# AdaPoon.net
KiCad netlist of a schematic drawn in EAGLE
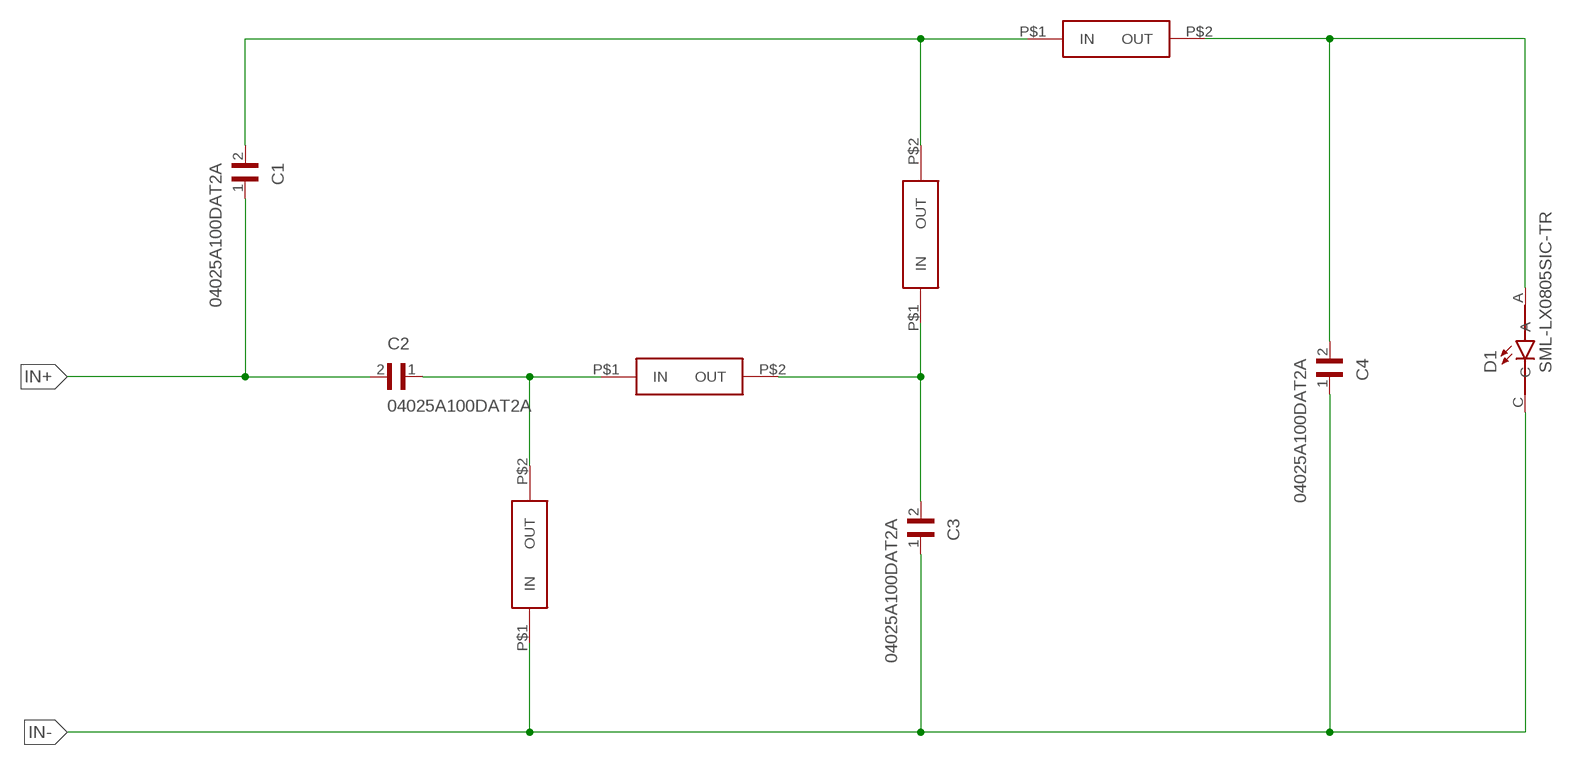
[diagram p0: schematic, sheet 1]

(export (version "E")
  (design (tool "Eeschema 10.0.6"))
  (components
    (comp (ref "C1")
      (value "04025A100DAT2A")
      (footprint "eagle-import:CAPC1005X56N")
      (fields (field (name "MF") "AVX"))
      (libsource (lib "eagle-import") (part "04025A100DAT2A"))
    )
    (comp (ref "C2")
      (value "04025A100DAT2A")
      (footprint "eagle-import:CAPC1005X56N")
      (fields (field (name "MF") "AVX"))
      (libsource (lib "eagle-import") (part "04025A100DAT2A"))
    )
    (comp (ref "C3")
      (value "04025A100DAT2A")
      (footprint "eagle-import:CAPC1005X56N")
      (fields (field (name "MF") "AVX"))
      (libsource (lib "eagle-import") (part "04025A100DAT2A"))
    )
    (comp (ref "C4")
      (value "04025A100DAT2A")
      (footprint "eagle-import:CAPC1005X56N")
      (fields (field (name "MF") "AVX"))
      (libsource (lib "eagle-import") (part "04025A100DAT2A"))
    )
    (comp (ref "D1")
      (value "SML-LX0805SIC-TR")
      (footprint "eagle-import:LEDC2012X120N")
      (fields (field (name "MF") "Lumex Opto/Components"))
      (libsource (lib "eagle-import") (part "SML-LX0805SIC-TR"))
    )
    (comp (ref "U$1")
      (value "SCHOTTKY0402")
      (footprint "eagle-import:0402_MURATA")
      (libsource (lib "eagle-import") (part "SCHOTTKY0402"))
    )
    (comp (ref "U$2")
      (value "SCHOTTKY0402")
      (footprint "eagle-import:0402_MURATA")
      (libsource (lib "eagle-import") (part "SCHOTTKY0402"))
    )
    (comp (ref "U$3")
      (value "SCHOTTKY0402")
      (footprint "eagle-import:0402_MURATA")
      (libsource (lib "eagle-import") (part "SCHOTTKY0402"))
    )
    (comp (ref "U$4")
      (value "SCHOTTKY0402")
      (footprint "eagle-import:0402_MURATA")
      (libsource (lib "eagle-import") (part "SCHOTTKY0402"))
    )
  )
  (nets
    (net (code "1") (name "IN+") (class "Default")
      (node (ref "C1") (pin "1") (pinfunction "1_1") (pintype "passive"))
      (node (ref "C2") (pin "2") (pinfunction "2_2") (pintype "passive"))
    )
    (net (code "2") (name "IN-") (class "Default")
      (node (ref "C3") (pin "1") (pinfunction "1_1") (pintype "passive"))
      (node (ref "C4") (pin "1") (pinfunction "1_1") (pintype "passive"))
      (node (ref "D1") (pin "C") (pinfunction "C_C") (pintype "passive"))
      (node (ref "U$1") (pin "P$1") (pinfunction "IN_P$1") (pintype "bidirectional"))
    )
    (net (code "3") (name "Net-(U$1-OUT)") (class "Default")
      (node (ref "C2") (pin "1") (pinfunction "1_1") (pintype "passive"))
      (node (ref "U$1") (pin "P$2") (pinfunction "OUT_P$2") (pintype "bidirectional"))
      (node (ref "U$2") (pin "P$1") (pinfunction "IN_P$1") (pintype "bidirectional"))
    )
    (net (code "4") (name "Net-(U$2-OUT)") (class "Default")
      (node (ref "C3") (pin "2") (pinfunction "2_2") (pintype "passive"))
      (node (ref "U$2") (pin "P$2") (pinfunction "OUT_P$2") (pintype "bidirectional"))
      (node (ref "U$3") (pin "P$1") (pinfunction "IN_P$1") (pintype "bidirectional"))
    )
    (net (code "5") (name "Net-(U$3-OUT)") (class "Default")
      (node (ref "C1") (pin "2") (pinfunction "2_2") (pintype "passive"))
      (node (ref "U$3") (pin "P$2") (pinfunction "OUT_P$2") (pintype "bidirectional"))
      (node (ref "U$4") (pin "P$1") (pinfunction "IN_P$1") (pintype "bidirectional"))
    )
    (net (code "6") (name "Net-(U$4-OUT)") (class "Default")
      (node (ref "C4") (pin "2") (pinfunction "2_2") (pintype "passive"))
      (node (ref "D1") (pin "A") (pinfunction "A_A") (pintype "passive"))
      (node (ref "U$4") (pin "P$2") (pinfunction "OUT_P$2") (pintype "bidirectional"))
    )
  )
)
